# MAX31826.net
KiCad netlist of a schematic drawn in Altium Designer
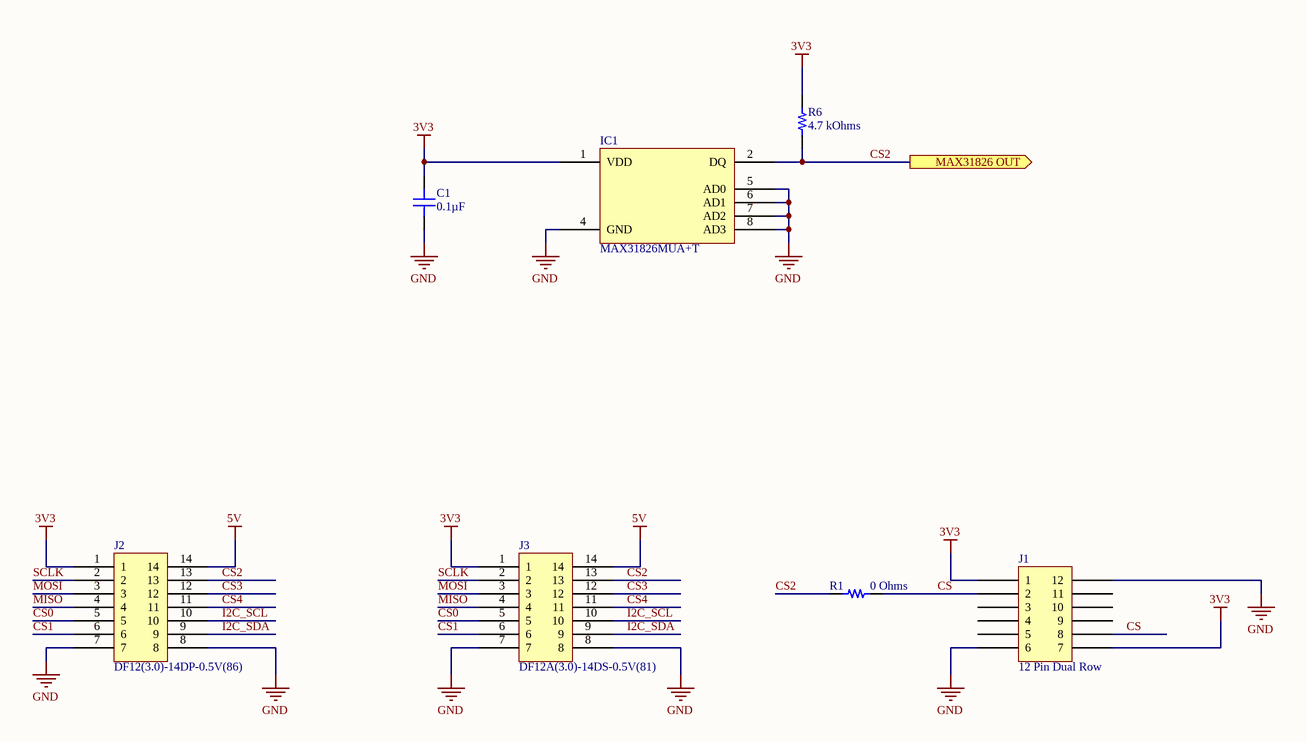
[diagram p0: MAX31826.SchDoc]

(export (version "E")
  (design (tool "Eeschema 10.0.6"))
  (components
    (comp (ref "C1")
      (value "0.1µF")
      (footprint "CAP 0603_1608")
      (description "CAP CER 0.1UF 16V Y5V 0603")
      (fields (field (name "PART NUMBER") "CC0603ZRY5V7BB104") (field (name "MANUFACTURER") "Yageo"))
      (libsource (lib "altiumlibrary.com") (part "Capacitor"))
    )
    (comp (ref "IC1")
      (value "MAX31826MUA+T")
      (footprint "MAXIM MSOP-8 uMAX")
      (description "SENSOR DIGITAL -55C-125C 8UMAX")
      (fields (field (name "MANUFACTURER") "Maxim Integrated"))
      (libsource (lib "altiumlibrary.com") (part "Maxim MAX31826"))
    )
    (comp (ref "J1")
      (value "12 Pin Dual Row")
      (footprint "TE 5650118-3 Card Edge")
      (libsource (lib "CelestialUseful") (part "12 Pin Dual Row"))
    )
    (comp (ref "J2")
      (value "DF12(3.0)-14DP-0.5V(86)")
      (footprint "HIROSE DF12 3.0-14DP-0.5V 86")
      (description "CONN HDR 14POS SMD GOLD")
      (fields (field (name "MANUFACTURER") "Hirose Electric Co Ltd"))
      (libsource (lib "altiumlibrary.com") (part "14 Pin Dual Row"))
    )
    (comp (ref "J3")
      (value "DF12A(3.0)-14DS-0.5V(81)")
      (footprint "HIROSE DF12A 3.0-14DS-0.5V 81")
      (description "CONN RCPT 14POS SMD GOLD")
      (fields (field (name "MANUFACTURER") "Hirose Electric Co Ltd"))
      (libsource (lib "altiumlibrary.com") (part "14 Pin Dual Row"))
    )
    (comp (ref "R1")
      (value "0 Ohms")
      (footprint "RES 0603_1608")
      (description "RES SMD 0 OHM JUMPER 1/10W 0603")
      (fields
        (field (name "PART NUMBER") "ERJ-3GEY0R00V")
        (field (name "MANUFACTURER") "Panasonic Electronic Components")
      )
      (libsource (lib "altiumlibrary.com") (part "Resistor"))
    )
    (comp (ref "R6")
      (value "4.7 kOhms")
      (footprint "RES 0603_1608")
      (description "RES SMD 4.7K OHM 1% 1/10W 0603")
      (fields
        (field (name "PART NUMBER") "ERJ-3EKF4701V")
        (field (name "MANUFACTURER") "Panasonic Electronic Components")
      )
      (libsource (lib "altiumlibrary.com") (part "Resistor"))
    )
  )
  (nets
    (net (code "1") (name "/CS") (class "Default")
      (node (ref "J1") (pin "2") (pinfunction "2_2") (pintype "passive"))
      (node (ref "J1") (pin "8") (pinfunction "8_8") (pintype "passive"))
      (node (ref "R1") (pin "2") (pinfunction "2_2") (pintype "passive"))
    )
    (net (code "2") (name "/CS0") (class "Default")
      (node (ref "J2") (pin "5") (pinfunction "5_5") (pintype "passive"))
      (node (ref "J3") (pin "5") (pinfunction "5_5") (pintype "passive"))
    )
    (net (code "3") (name "/CS1") (class "Default")
      (node (ref "J2") (pin "6") (pinfunction "6_6") (pintype "passive"))
      (node (ref "J3") (pin "6") (pinfunction "6_6") (pintype "passive"))
    )
    (net (code "4") (name "/CS2") (class "Default")
      (node (ref "IC1") (pin "2") (pinfunction "DQ_2") (pintype "passive"))
      (node (ref "J2") (pin "13") (pinfunction "13_13") (pintype "passive"))
      (node (ref "J3") (pin "13") (pinfunction "13_13") (pintype "passive"))
      (node (ref "R1") (pin "1") (pinfunction "1_1") (pintype "passive"))
      (node (ref "R6") (pin "1") (pinfunction "1_1") (pintype "passive"))
    )
    (net (code "5") (name "/CS3") (class "Default")
      (node (ref "J2") (pin "12") (pinfunction "12_12") (pintype "passive"))
      (node (ref "J3") (pin "12") (pinfunction "12_12") (pintype "passive"))
    )
    (net (code "6") (name "/CS4") (class "Default")
      (node (ref "J2") (pin "11") (pinfunction "11_11") (pintype "passive"))
      (node (ref "J3") (pin "11") (pinfunction "11_11") (pintype "passive"))
    )
    (net (code "7") (name "/I2C_SCL") (class "Default")
      (node (ref "J2") (pin "10") (pinfunction "10_10") (pintype "passive"))
      (node (ref "J3") (pin "10") (pinfunction "10_10") (pintype "passive"))
    )
    (net (code "8") (name "/I2C_SDA") (class "Default")
      (node (ref "J2") (pin "9") (pinfunction "9_9") (pintype "passive"))
      (node (ref "J3") (pin "9") (pinfunction "9_9") (pintype "passive"))
    )
    (net (code "9") (name "/MISO") (class "Default")
      (node (ref "J2") (pin "4") (pinfunction "4_4") (pintype "passive"))
      (node (ref "J3") (pin "4") (pinfunction "4_4") (pintype "passive"))
    )
    (net (code "10") (name "/MOSI") (class "Default")
      (node (ref "J2") (pin "3") (pinfunction "3_3") (pintype "passive"))
      (node (ref "J3") (pin "3") (pinfunction "3_3") (pintype "passive"))
    )
    (net (code "11") (name "/SCLK") (class "Default")
      (node (ref "J2") (pin "2") (pinfunction "2_2") (pintype "passive"))
      (node (ref "J3") (pin "2") (pinfunction "2_2") (pintype "passive"))
    )
    (net (code "12") (name "3V3") (class "Default")
      (node (ref "C1") (pin "1") (pinfunction "1_1") (pintype "passive"))
      (node (ref "IC1") (pin "1") (pinfunction "VDD_1") (pintype "passive"))
      (node (ref "J1") (pin "1") (pinfunction "1_1") (pintype "passive"))
      (node (ref "J1") (pin "7") (pinfunction "7_7") (pintype "passive"))
      (node (ref "J2") (pin "1") (pinfunction "1_1") (pintype "passive"))
      (node (ref "J3") (pin "1") (pinfunction "1_1") (pintype "passive"))
      (node (ref "R6") (pin "2") (pinfunction "2_2") (pintype "passive"))
    )
    (net (code "13") (name "5V") (class "Default")
      (node (ref "J2") (pin "14") (pinfunction "14_14") (pintype "passive"))
      (node (ref "J3") (pin "14") (pinfunction "14_14") (pintype "passive"))
    )
    (net (code "14") (name "GND") (class "Default")
      (node (ref "C1") (pin "2") (pinfunction "2_2") (pintype "passive"))
      (node (ref "IC1") (pin "4") (pinfunction "GND_4") (pintype "passive"))
      (node (ref "IC1") (pin "5") (pinfunction "AD0_5") (pintype "passive"))
      (node (ref "IC1") (pin "6") (pinfunction "AD1_6") (pintype "passive"))
      (node (ref "IC1") (pin "7") (pinfunction "AD2_7") (pintype "passive"))
      (node (ref "IC1") (pin "8") (pinfunction "AD3_8") (pintype "passive"))
      (node (ref "J1") (pin "12") (pinfunction "12_12") (pintype "passive"))
      (node (ref "J1") (pin "6") (pinfunction "6_6") (pintype "passive"))
      (node (ref "J2") (pin "7") (pinfunction "7_7") (pintype "passive"))
      (node (ref "J2") (pin "8") (pinfunction "8_8") (pintype "passive"))
      (node (ref "J3") (pin "7") (pinfunction "7_7") (pintype "passive"))
      (node (ref "J3") (pin "8") (pinfunction "8_8") (pintype "passive"))
    )
    (net (code "15") (name "unconnected-(J1-Pad3)") (class "Default")
      (node (ref "J1") (pin "3") (pinfunction "3_3") (pintype "passive"))
    )
    (net (code "16") (name "unconnected-(J1-Pad4)") (class "Default")
      (node (ref "J1") (pin "4") (pinfunction "4_4") (pintype "passive"))
    )
    (net (code "17") (name "unconnected-(J1-Pad5)") (class "Default")
      (node (ref "J1") (pin "5") (pinfunction "5_5") (pintype "passive"))
    )
    (net (code "18") (name "unconnected-(J1-Pad9)") (class "Default")
      (node (ref "J1") (pin "9") (pinfunction "9_9") (pintype "passive"))
    )
    (net (code "19") (name "unconnected-(J1-Pad10)") (class "Default")
      (node (ref "J1") (pin "10") (pinfunction "10_10") (pintype "passive"))
    )
    (net (code "20") (name "unconnected-(J1-Pad11)") (class "Default")
      (node (ref "J1") (pin "11") (pinfunction "11_11") (pintype "passive"))
    )
  )
)
